# PCB1_BioTron.net
KiCad netlist of a schematic drawn in Altium Designer
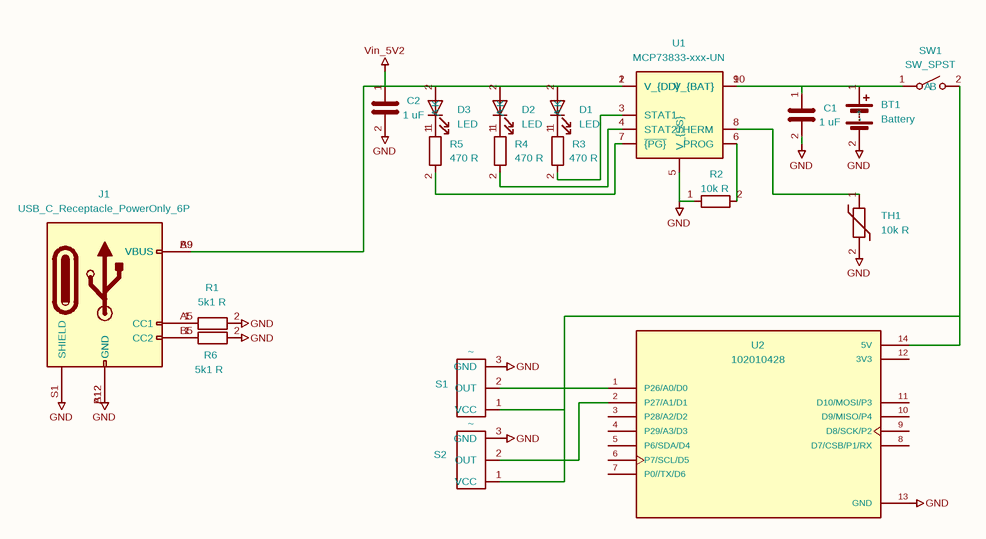
[diagram p0: PCB1_BioTron.SchDoc]

(export (version "E")
  (design (tool "Eeschema 10.0.6"))
  (components
    (comp (ref "BT1")
      (value "Battery")
      (description "Multiple-cell battery")
      (libsource (lib "Device") (part "Battery"))
    )
    (comp (ref "C1")
      (value "1 uF")
      (description "Unpolarized capacitor")
      (libsource (lib "Device") (part "C"))
    )
    (comp (ref "C2")
      (value "1 uF")
      (description "Unpolarized capacitor")
      (libsource (lib "Device") (part "C"))
    )
    (comp (ref "D1")
      (value "LED")
      (description "Light emitting diode")
      (libsource (lib "Device") (part "LED"))
    )
    (comp (ref "D2")
      (value "LED")
      (description "Light emitting diode")
      (libsource (lib "Device") (part "LED"))
    )
    (comp (ref "D3")
      (value "LED")
      (description "Light emitting diode")
      (libsource (lib "Device") (part "LED"))
    )
    (comp (ref "J1")
      (value "USB_C_Receptacle_PowerOnly_6P")
      (description "USB Power-Only 6P Type-C Receptacle connector")
      (libsource (lib "Connector") (part "USB_C_Receptacle_PowerOnly_6P"))
    )
    (comp (ref "R1") (value "5k1 R") (description "Resistor") (libsource (lib "Device") (part "R")))
    (comp (ref "R2") (value "10k R") (description "Resistor") (libsource (lib "Device") (part "R")))
    (comp (ref "R3") (value "470 R") (description "Resistor") (libsource (lib "") (part "R_1")))
    (comp (ref "R4") (value "470 R") (description "Resistor") (libsource (lib "") (part "R_1")))
    (comp (ref "R5") (value "470 R") (description "Resistor") (libsource (lib "") (part "R_1")))
    (comp (ref "R6") (value "5k1 R") (description "Resistor") (libsource (lib "Device") (part "R")))
    (comp (ref "S1") (value "~") (libsource (lib "Epic_Library") (part "myoware2")))
    (comp (ref "S2") (value "~") (libsource (lib "Epic_Library") (part "myoware2")))
    (comp (ref "SW1")
      (value "SW_SPST")
      (description "Single Pole Single Throw (SPST) switch")
      (libsource (lib "Switch") (part "SW_SPST"))
    )
    (comp (ref "TH1")
      (value "10k R")
      (description "Temperature dependent resistor")
      (libsource (lib "Device") (part "Thermistor"))
    )
    (comp (ref "U1")
      (value "MCP73833-xxx-UN")
      (description "Stand-Alone Linear Li-Ion / Li-Polymer Charge Management Controller, MSOP-10")
      (libsource (lib "Battery_Management") (part "MCP73833-xxx-UN"))
    )
    (comp (ref "U2")
      (value "102010428")
      (fields (field (name "MF") "Seeed Technology Co., Ltd") (field (name "MANUFACTURER") "Seeedstudio"))
      (libsource (lib "ESP32-C-mini") (part "102010428"))
    )
  )
  (nets
    (net (code "1") (name "GND") (class "Default")
      (node (ref "BT1") (pin "2") (pinfunction "-_2") (pintype "passive"))
      (node (ref "C1") (pin "2") (pinfunction "2_2") (pintype "passive"))
      (node (ref "C2") (pin "2") (pinfunction "2_2") (pintype "passive"))
      (node (ref "J1") (pin "A12") (pinfunction "GND_A12") (pintype "passive"))
      (node (ref "J1") (pin "B12") (pinfunction "GND_B12") (pintype "passive"))
      (node (ref "J1") (pin "S1") (pinfunction "SHIELD_S1") (pintype "passive"))
      (node (ref "R1") (pin "2") (pinfunction "2_2") (pintype "passive"))
      (node (ref "R2") (pin "1") (pinfunction "1_1") (pintype "passive"))
      (node (ref "R6") (pin "2") (pinfunction "2_2") (pintype "passive"))
      (node (ref "S1") (pin "3") (pinfunction "GND_3") (pintype "passive"))
      (node (ref "S2") (pin "3") (pinfunction "GND_3") (pintype "passive"))
      (node (ref "TH1") (pin "2") (pinfunction "2_2") (pintype "passive"))
      (node (ref "U1") (pin "5") (pinfunction "V_{SS}_5") (pintype "passive"))
      (node (ref "U2") (pin "13") (pinfunction "GND_13") (pintype "passive"))
    )
    (net (code "2") (name "Net-(BT1-+)") (class "Default")
      (node (ref "BT1") (pin "1") (pinfunction "+_1") (pintype "passive"))
      (node (ref "C1") (pin "1") (pinfunction "1_1") (pintype "passive"))
      (node (ref "SW1") (pin "1") (pinfunction "A_1") (pintype "passive"))
      (node (ref "U1") (pin "10") (pinfunction "V_{BAT}_10") (pintype "passive"))
      (node (ref "U1") (pin "9") (pinfunction "V_{BAT}_9") (pintype "passive"))
    )
    (net (code "3") (name "Net-(D1-K)") (class "Default")
      (node (ref "D1") (pin "1") (pinfunction "K_1") (pintype "passive"))
      (node (ref "R3") (pin "1") (pinfunction "1_1") (pintype "passive"))
    )
    (net (code "4") (name "Net-(D2-K)") (class "Default")
      (node (ref "D2") (pin "1") (pinfunction "K_1") (pintype "passive"))
      (node (ref "R4") (pin "1") (pinfunction "1_1") (pintype "passive"))
    )
    (net (code "5") (name "Net-(D3-K)") (class "Default")
      (node (ref "D3") (pin "1") (pinfunction "K_1") (pintype "passive"))
      (node (ref "R5") (pin "1") (pinfunction "1_1") (pintype "passive"))
    )
    (net (code "6") (name "Net-(J1-CC1)") (class "Default")
      (node (ref "J1") (pin "A5") (pinfunction "CC1_A5") (pintype "passive"))
      (node (ref "R1") (pin "1") (pinfunction "1_1") (pintype "passive"))
    )
    (net (code "7") (name "Net-(J1-CC2)") (class "Default")
      (node (ref "J1") (pin "B5") (pinfunction "CC2_B5") (pintype "passive"))
      (node (ref "R6") (pin "1") (pinfunction "1_1") (pintype "passive"))
    )
    (net (code "8") (name "Net-(S1-OUT)") (class "Default")
      (node (ref "S1") (pin "2") (pinfunction "OUT_2") (pintype "passive"))
      (node (ref "U2") (pin "1") (pinfunction "P26/A0/D0_1") (pintype "passive"))
    )
    (net (code "9") (name "Net-(S1-VCC)") (class "Default")
      (node (ref "S1") (pin "1") (pinfunction "VCC_1") (pintype "passive"))
      (node (ref "S2") (pin "1") (pinfunction "VCC_1") (pintype "passive"))
      (node (ref "SW1") (pin "2") (pinfunction "B_2") (pintype "passive"))
      (node (ref "U2") (pin "14") (pinfunction "5V_14") (pintype "passive"))
    )
    (net (code "10") (name "Net-(S2-OUT)") (class "Default")
      (node (ref "S2") (pin "2") (pinfunction "OUT_2") (pintype "passive"))
      (node (ref "U2") (pin "2") (pinfunction "P27/A1/D1_2") (pintype "passive"))
    )
    (net (code "11") (name "Net-(U1-PROG)") (class "Default")
      (node (ref "R2") (pin "2") (pinfunction "2_2") (pintype "passive"))
      (node (ref "U1") (pin "6") (pinfunction "PROG_6") (pintype "passive"))
    )
    (net (code "12") (name "Net-(U1-STAT1)") (class "Default")
      (node (ref "R3") (pin "2") (pinfunction "2_2") (pintype "passive"))
      (node (ref "U1") (pin "3") (pinfunction "STAT1_3") (pintype "passive"))
    )
    (net (code "13") (name "Net-(U1-STAT2)") (class "Default")
      (node (ref "R4") (pin "2") (pinfunction "2_2") (pintype "passive"))
      (node (ref "U1") (pin "4") (pinfunction "STAT2_4") (pintype "passive"))
    )
    (net (code "14") (name "Net-(U1-THERM)") (class "Default")
      (node (ref "TH1") (pin "1") (pinfunction "1_1") (pintype "passive"))
      (node (ref "U1") (pin "8") (pinfunction "THERM_8") (pintype "passive"))
    )
    (net (code "15") (name "Net-(U1-~{{PG}})") (class "Default")
      (node (ref "R5") (pin "2") (pinfunction "2_2") (pintype "passive"))
      (node (ref "U1") (pin "7") (pinfunction "~{{PG}}_7") (pintype "passive"))
    )
    (net (code "16") (name "Vin_5V2") (class "Default")
      (node (ref "C2") (pin "1") (pinfunction "1_1") (pintype "passive"))
      (node (ref "D1") (pin "2") (pinfunction "A_2") (pintype "passive"))
      (node (ref "D2") (pin "2") (pinfunction "A_2") (pintype "passive"))
      (node (ref "D3") (pin "2") (pinfunction "A_2") (pintype "passive"))
      (node (ref "J1") (pin "A9") (pinfunction "VBUS_A9") (pintype "passive"))
      (node (ref "J1") (pin "B9") (pinfunction "VBUS_B9") (pintype "passive"))
      (node (ref "U1") (pin "1") (pinfunction "V_{DD}_1") (pintype "passive"))
      (node (ref "U1") (pin "2") (pinfunction "V_{DD}_2") (pintype "passive"))
    )
    (net (code "17") (name "unconnected-(U2-3V3-Pad12)") (class "Default")
      (node (ref "U2") (pin "12") (pinfunction "3V3_12") (pintype "passive"))
    )
    (net (code "18") (name "unconnected-(U2-D7{slash}CSB{slash}P1{slash}RX-Pad8)") (class "Default")
      (node (ref "U2") (pin "8") (pinfunction "D7/CSB/P1/RX_8") (pintype "passive"))
    )
    (net (code "19") (name "unconnected-(U2-D8{slash}SCK{slash}P2-Pad9)") (class "Default")
      (node (ref "U2") (pin "9") (pinfunction "D8/SCK/P2_9") (pintype "passive"))
    )
    (net (code "20") (name "unconnected-(U2-D9{slash}MISO{slash}P4-Pad10)") (class "Default")
      (node (ref "U2") (pin "10") (pinfunction "D9/MISO/P4_10") (pintype "passive"))
    )
    (net (code "21") (name "unconnected-(U2-D10{slash}MOSI{slash}P3-Pad11)") (class "Default")
      (node (ref "U2") (pin "11") (pinfunction "D10/MOSI/P3_11") (pintype "passive"))
    )
    (net (code "22") (name "unconnected-(U2-P0{slash}{slash}TX{slash}D6-Pad7)") (class "Default")
      (node (ref "U2") (pin "7") (pinfunction "P0//TX/D6_7") (pintype "passive"))
    )
    (net (code "23") (name "unconnected-(U2-P6{slash}SDA{slash}D4-Pad5)") (class "Default")
      (node (ref "U2") (pin "5") (pinfunction "P6/SDA/D4_5") (pintype "passive"))
    )
    (net (code "24") (name "unconnected-(U2-P7{slash}SCL{slash}D5-Pad6)") (class "Default")
      (node (ref "U2") (pin "6") (pinfunction "P7/SCL/D5_6") (pintype "passive"))
    )
    (net (code "25") (name "unconnected-(U2-P28{slash}A2{slash}D2-Pad3)") (class "Default")
      (node (ref "U2") (pin "3") (pinfunction "P28/A2/D2_3") (pintype "passive"))
    )
    (net (code "26") (name "unconnected-(U2-P29{slash}A3{slash}D3-Pad4)") (class "Default")
      (node (ref "U2") (pin "4") (pinfunction "P29/A3/D3_4") (pintype "passive"))
    )
  )
)
